# Qwiic_Quad_Relay.net
KiCad netlist of a schematic drawn in EAGLE
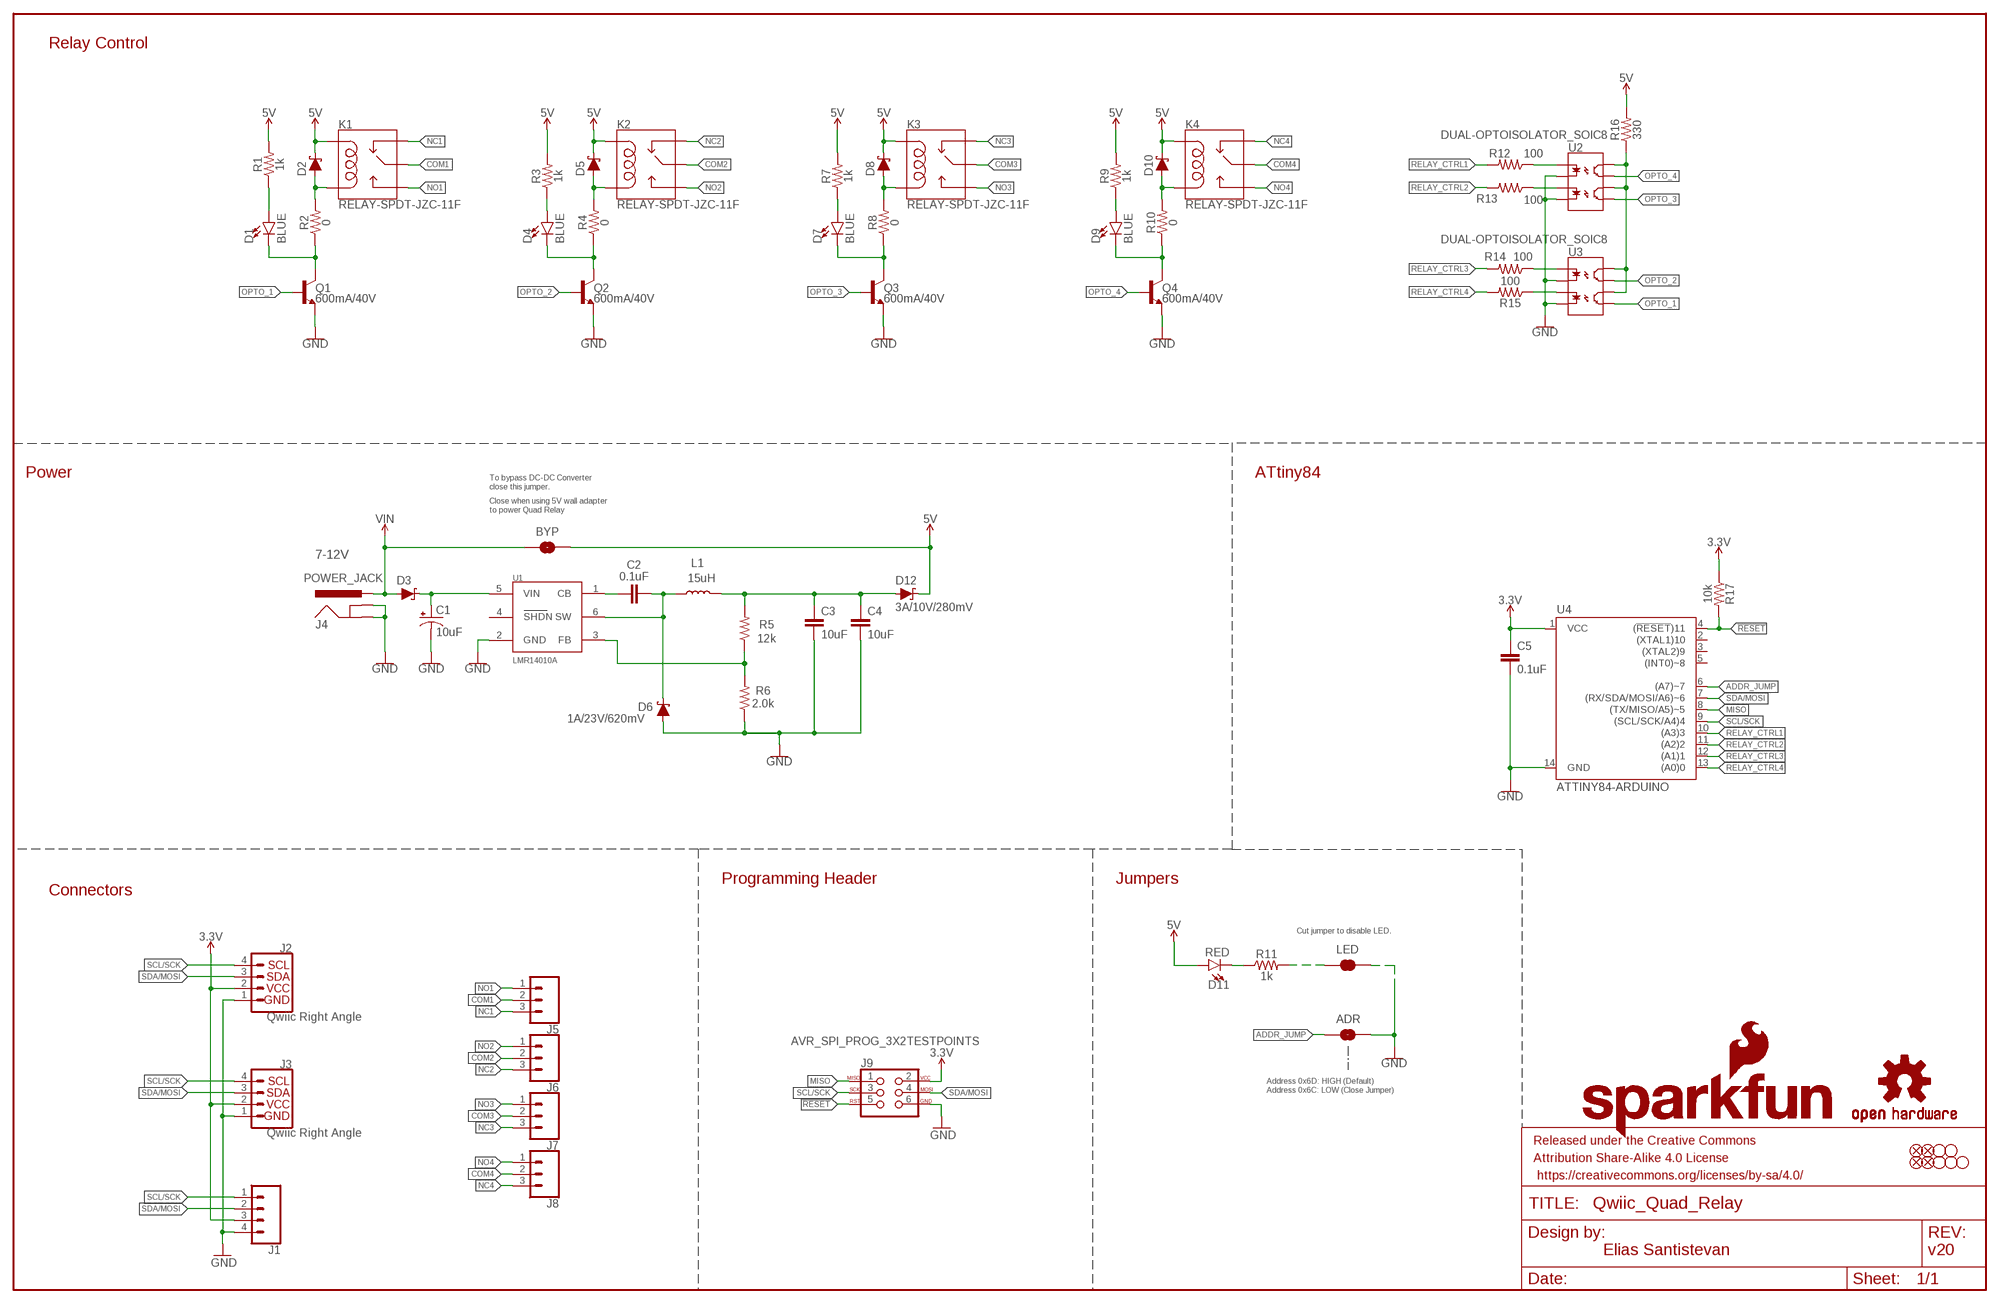
[diagram p0: schematic, sheet 1]

(export (version "E")
  (design (tool "Eeschema 10.0.6"))
  (components
    (comp (ref "ADR")
      (value "JUMPER-SMT_2_NO_SILK")
      (footprint "eagle-import:SMT-JUMPER_2_NO_SILK")
      (libsource (lib "eagle-import") (part "JUMPER-SMT_2_NO_SILK"))
    )
    (comp (ref "BYP")
      (value "JUMPER-SMT_2_NO_SILK")
      (footprint "eagle-import:SMT-JUMPER_2_NO_SILK")
      (libsource (lib "eagle-import") (part "JUMPER-SMT_2_NO_SILK"))
    )
    (comp (ref "C1")
      (value "10uF")
      (footprint "eagle-import:EIA3528")
      (libsource (lib "eagle-import") (part "10UF-POLAR-EIA3528-20V-10%(TANT)"))
    )
    (comp (ref "C2")
      (value "0.1uF")
      (footprint "eagle-import:0402")
      (libsource (lib "eagle-import") (part "0.1UF-0402-10V-10%-X7R"))
    )
    (comp (ref "C3")
      (value "10uF")
      (footprint "eagle-import:0603")
      (libsource (lib "eagle-import") (part "10UF-0603-6.3V-20%"))
    )
    (comp (ref "C4")
      (value "10uF")
      (footprint "eagle-import:0603")
      (libsource (lib "eagle-import") (part "10UF-0603-6.3V-20%"))
    )
    (comp (ref "C5")
      (value "0.1uF")
      (footprint "eagle-import:0603")
      (libsource (lib "eagle-import") (part "0.1UF-0603-25V-(+80/-20%)"))
    )
    (comp (ref "D1")
      (value "BLUE")
      (footprint "eagle-import:LED-0603")
      (libsource (lib "eagle-import") (part "LED-BLUE0603"))
    )
    (comp (ref "D2")
      (value "1A/23V/620mV")
      (footprint "eagle-import:SOD-323")
      (libsource (lib "eagle-import") (part "DIODE-SCHOTTKY-BAT20J"))
    )
    (comp (ref "D3")
      (value "1A/40V/500mV")
      (footprint "eagle-import:SMA-DIODE")
      (libsource (lib "eagle-import") (part "DIODE-SCHOTTKY-SS14"))
    )
    (comp (ref "D4")
      (value "BLUE")
      (footprint "eagle-import:LED-0603")
      (libsource (lib "eagle-import") (part "LED-BLUE0603"))
    )
    (comp (ref "D5")
      (value "1A/23V/620mV")
      (footprint "eagle-import:SOD-323")
      (libsource (lib "eagle-import") (part "DIODE-SCHOTTKY-BAT20J"))
    )
    (comp (ref "D6")
      (value "1A/23V/620mV")
      (footprint "eagle-import:SOD-323")
      (libsource (lib "eagle-import") (part "DIODE-SCHOTTKY-BAT20J"))
    )
    (comp (ref "D7")
      (value "BLUE")
      (footprint "eagle-import:LED-0603")
      (libsource (lib "eagle-import") (part "LED-BLUE0603"))
    )
    (comp (ref "D8")
      (value "1A/23V/620mV")
      (footprint "eagle-import:SOD-323")
      (libsource (lib "eagle-import") (part "DIODE-SCHOTTKY-BAT20J"))
    )
    (comp (ref "D9")
      (value "BLUE")
      (footprint "eagle-import:LED-0603")
      (libsource (lib "eagle-import") (part "LED-BLUE0603"))
    )
    (comp (ref "D10")
      (value "1A/23V/620mV")
      (footprint "eagle-import:SOD-323")
      (libsource (lib "eagle-import") (part "DIODE-SCHOTTKY-BAT20J"))
    )
    (comp (ref "D11")
      (value "RED")
      (footprint "eagle-import:LED-0603")
      (libsource (lib "eagle-import") (part "LED-RED0603"))
    )
    (comp (ref "D12")
      (value "3A/10V/280mV")
      (footprint "eagle-import:SOD-323")
      (libsource (lib "eagle-import") (part "DIODE-SCHOTTKY-BAT60A"))
    )
    (comp (ref "FD1")
      (value "FIDUCIAL1X2")
      (footprint "eagle-import:FIDUCIAL-1X2")
      (libsource (lib "eagle-import") (part "FIDUCIAL1X2"))
    )
    (comp (ref "FD2")
      (value "FIDUCIAL1X2")
      (footprint "eagle-import:FIDUCIAL-1X2")
      (libsource (lib "eagle-import") (part "FIDUCIAL1X2"))
    )
    (comp (ref "FD3")
      (value "FIDUCIAL1X2")
      (footprint "eagle-import:FIDUCIAL-1X2")
      (libsource (lib "eagle-import") (part "FIDUCIAL1X2"))
    )
    (comp (ref "FD4")
      (value "FIDUCIAL1X2")
      (footprint "eagle-import:FIDUCIAL-1X2")
      (libsource (lib "eagle-import") (part "FIDUCIAL1X2"))
    )
    (comp (ref "FRAME1")
      (value "FRAME-LEDGER")
      (footprint "eagle-import:CREATIVE_COMMONS")
      (libsource (lib "eagle-import") (part "FRAME-LEDGER"))
    )
    (comp (ref "J1")
      (value "CONN_041X04_NO_SILK_NO_POP")
      (footprint "eagle-import:1X04_NO_SILK")
      (libsource (lib "eagle-import") (part "CONN_041X04_NO_SILK_NO_POP"))
    )
    (comp (ref "J2")
      (value "Qwiic Right Angle")
      (footprint "eagle-import:JST04_1MM_RA")
      (libsource (lib "eagle-import") (part "I2C_STANDARDQWIIC"))
    )
    (comp (ref "J3")
      (value "Qwiic Right Angle")
      (footprint "eagle-import:JST04_1MM_RA")
      (libsource (lib "eagle-import") (part "I2C_STANDARDQWIIC"))
    )
    (comp (ref "J4")
      (value "POWER_JACK")
      (footprint "eagle-import:POWER_JACK_PTH")
      (libsource (lib "eagle-import") (part "POWER_JACK"))
    )
    (comp (ref "J5")
      (value "CONN_03-SCREW-5MM")
      (footprint "eagle-import:SCREWTERMINAL-5MM-3")
      (libsource (lib "eagle-import") (part "CONN_03-SCREW-5MM"))
    )
    (comp (ref "J6")
      (value "CONN_03-SCREW-5MM")
      (footprint "eagle-import:SCREWTERMINAL-5MM-3")
      (libsource (lib "eagle-import") (part "CONN_03-SCREW-5MM"))
    )
    (comp (ref "J7")
      (value "CONN_03-SCREW-5MM")
      (footprint "eagle-import:SCREWTERMINAL-5MM-3")
      (libsource (lib "eagle-import") (part "CONN_03-SCREW-5MM"))
    )
    (comp (ref "J8")
      (value "CONN_03-SCREW-5MM")
      (footprint "eagle-import:SCREWTERMINAL-5MM-3")
      (libsource (lib "eagle-import") (part "CONN_03-SCREW-5MM"))
    )
    (comp (ref "J9")
      (value "AVR_SPI_PROG_3X2TESTPOINTS")
      (footprint "eagle-import:2X3_TEST_POINTS")
      (libsource (lib "eagle-import") (part "AVR_SPI_PROG_3X2TESTPOINTS"))
    )
    (comp (ref "JP1")
      (value "STAND-OFF")
      (footprint "eagle-import:STAND-OFF")
      (libsource (lib "eagle-import") (part "STAND-OFF"))
    )
    (comp (ref "JP4")
      (value "STAND-OFF")
      (footprint "eagle-import:STAND-OFF")
      (libsource (lib "eagle-import") (part "STAND-OFF"))
    )
    (comp (ref "JP5")
      (value "STAND-OFF")
      (footprint "eagle-import:STAND-OFF")
      (libsource (lib "eagle-import") (part "STAND-OFF"))
    )
    (comp (ref "JP6")
      (value "STAND-OFF")
      (footprint "eagle-import:STAND-OFF")
      (libsource (lib "eagle-import") (part "STAND-OFF"))
    )
    (comp (ref "JP7")
      (value "STAND-OFF")
      (footprint "eagle-import:STAND-OFF")
      (libsource (lib "eagle-import") (part "STAND-OFF"))
    )
    (comp (ref "K1")
      (value "RELAY-SPDT-JZC-11F")
      (footprint "eagle-import:RELAY-JZC")
      (libsource (lib "eagle-import") (part "RELAY-SPDT-JZC-11F"))
    )
    (comp (ref "K2")
      (value "RELAY-SPDT-JZC-11F")
      (footprint "eagle-import:RELAY-JZC")
      (libsource (lib "eagle-import") (part "RELAY-SPDT-JZC-11F"))
    )
    (comp (ref "K3")
      (value "RELAY-SPDT-JZC-11F")
      (footprint "eagle-import:RELAY-JZC")
      (libsource (lib "eagle-import") (part "RELAY-SPDT-JZC-11F"))
    )
    (comp (ref "K4")
      (value "RELAY-SPDT-JZC-11F")
      (footprint "eagle-import:RELAY-JZC")
      (libsource (lib "eagle-import") (part "RELAY-SPDT-JZC-11F"))
    )
    (comp (ref "L1")
      (value "15uH")
      (footprint "eagle-import:INDUCTOR_15UH")
      (libsource (lib "eagle-import") (part "INDUCTOR-LQH5B-15UH"))
    )
    (comp (ref "LED")
      (value "JUMPER-SMT_2_NC_TRACE_SILK")
      (footprint "eagle-import:SMT-JUMPER_2_NC_TRACE_SILK")
      (libsource (lib "eagle-import") (part "JUMPER-SMT_2_NC_TRACE_SILK"))
    )
    (comp (ref "LOGO1")
      (value "SFE_LOGO_NAME_FLAME.1_INCH")
      (footprint "eagle-import:SFE_LOGO_NAME_FLAME_.1")
      (libsource (lib "eagle-import") (part "SFE_LOGO_NAME_FLAME.1_INCH"))
    )
    (comp (ref "LOGO2")
      (value "OSHW-LOGOS")
      (footprint "eagle-import:OSHW-LOGO-S")
      (libsource (lib "eagle-import") (part "OSHW-LOGOS"))
    )
    (comp (ref "Q1")
      (value "600mA/40V")
      (footprint "eagle-import:SOT23-3")
      (libsource (lib "eagle-import") (part "TRANS_NPN-MMBT2222AL"))
    )
    (comp (ref "Q2")
      (value "600mA/40V")
      (footprint "eagle-import:SOT23-3")
      (libsource (lib "eagle-import") (part "TRANS_NPN-MMBT2222AL"))
    )
    (comp (ref "Q3")
      (value "600mA/40V")
      (footprint "eagle-import:SOT23-3")
      (libsource (lib "eagle-import") (part "TRANS_NPN-MMBT2222AL"))
    )
    (comp (ref "Q4")
      (value "600mA/40V")
      (footprint "eagle-import:SOT23-3")
      (libsource (lib "eagle-import") (part "TRANS_NPN-MMBT2222AL"))
    )
    (comp (ref "R1")
      (value "1k")
      (footprint "eagle-import:0603")
      (libsource (lib "eagle-import") (part "1KOHM-0603-1/10W-1%"))
    )
    (comp (ref "R2")
      (value "0")
      (footprint "eagle-import:0603")
      (libsource (lib "eagle-import") (part "0OHM-0603-1/10W"))
    )
    (comp (ref "R3")
      (value "1k")
      (footprint "eagle-import:0603")
      (libsource (lib "eagle-import") (part "1KOHM-0603-1/10W-1%"))
    )
    (comp (ref "R4")
      (value "0")
      (footprint "eagle-import:0603")
      (libsource (lib "eagle-import") (part "0OHM-0603-1/10W"))
    )
    (comp (ref "R5")
      (value "12k")
      (footprint "eagle-import:0603")
      (libsource (lib "eagle-import") (part "12KOHM-0603-1/10W-1%"))
    )
    (comp (ref "R6")
      (value "2.0k")
      (footprint "eagle-import:0603")
      (libsource (lib "eagle-import") (part "2.0KOHM-0603-1/10W-5%"))
    )
    (comp (ref "R7")
      (value "1k")
      (footprint "eagle-import:0603")
      (libsource (lib "eagle-import") (part "1KOHM-0603-1/10W-1%"))
    )
    (comp (ref "R8")
      (value "0")
      (footprint "eagle-import:0603")
      (libsource (lib "eagle-import") (part "0OHM-0603-1/10W"))
    )
    (comp (ref "R9")
      (value "1k")
      (footprint "eagle-import:0603")
      (libsource (lib "eagle-import") (part "1KOHM-0603-1/10W-1%"))
    )
    (comp (ref "R10")
      (value "0")
      (footprint "eagle-import:0603")
      (libsource (lib "eagle-import") (part "0OHM-0603-1/10W"))
    )
    (comp (ref "R11")
      (value "1k")
      (footprint "eagle-import:0603")
      (libsource (lib "eagle-import") (part "1KOHM-0603-1/10W-1%"))
    )
    (comp (ref "R12")
      (value "100")
      (footprint "eagle-import:0603")
      (libsource (lib "eagle-import") (part "100OHM-0603-1/10W-1%"))
    )
    (comp (ref "R13")
      (value "100")
      (footprint "eagle-import:0603")
      (libsource (lib "eagle-import") (part "100OHM-0603-1/10W-1%"))
    )
    (comp (ref "R14")
      (value "100")
      (footprint "eagle-import:0603")
      (libsource (lib "eagle-import") (part "100OHM-0603-1/10W-1%"))
    )
    (comp (ref "R15")
      (value "100")
      (footprint "eagle-import:0603")
      (libsource (lib "eagle-import") (part "100OHM-0603-1/10W-1%"))
    )
    (comp (ref "R16")
      (value "330")
      (footprint "eagle-import:0603")
      (libsource (lib "eagle-import") (part "330OHM-0603-1/10W-1%"))
    )
    (comp (ref "R17")
      (value "10k")
      (footprint "eagle-import:0603")
      (libsource (lib "eagle-import") (part "10KOHM-0603-1/10W-1%"))
    )
    (comp (ref "U1")
      (value "LMR14010A")
      (footprint "eagle-import:SOT23-6")
      (libsource (lib "eagle-import") (part "LMR14010A"))
    )
    (comp (ref "U2")
      (value "DUAL-OPTOISOLATOR_SOIC8")
      (footprint "eagle-import:SO08")
      (libsource (lib "eagle-import") (part "DUAL-OPTOISOLATOR_SOIC8"))
    )
    (comp (ref "U3")
      (value "DUAL-OPTOISOLATOR_SOIC8")
      (footprint "eagle-import:SO08")
      (libsource (lib "eagle-import") (part "DUAL-OPTOISOLATOR_SOIC8"))
    )
    (comp (ref "U4")
      (value "ATTINY84-ARDUINO")
      (footprint "eagle-import:SO14")
      (libsource (lib "eagle-import") (part "ATTINY84-ARDUINO"))
    )
  )
  (nets
    (net (code "1") (name "/~{RESET}") (class "Default")
      (node (ref "J9") (pin "5") (pinfunction "5_5") (pintype "passive"))
      (node (ref "R17") (pin "2") (pinfunction "2_2") (pintype "passive"))
      (node (ref "U4") (pin "4") (pinfunction "(~{RESET})11_4") (pintype "bidirectional"))
    )
    (net (code "2") (name "3.3V") (class "Default")
      (node (ref "C5") (pin "1") (pinfunction "1_1") (pintype "passive"))
      (node (ref "J1") (pin "3") (pinfunction "3_3") (pintype "passive"))
      (node (ref "J2") (pin "2") (pinfunction "2_2") (pintype "power_in"))
      (node (ref "J3") (pin "2") (pinfunction "2_2") (pintype "power_in"))
      (node (ref "J9") (pin "2") (pinfunction "2_2") (pintype "passive"))
      (node (ref "R17") (pin "1") (pinfunction "1_1") (pintype "passive"))
      (node (ref "U4") (pin "1") (pinfunction "VCC_1") (pintype "bidirectional"))
    )
    (net (code "3") (name "5V") (class "Default")
      (node (ref "BYP") (pin "2") (pinfunction "2_2") (pintype "passive"))
      (node (ref "D10") (pin "C") (pinfunction "C_C") (pintype "passive"))
      (node (ref "D11") (pin "A") (pinfunction "A_A") (pintype "passive"))
      (node (ref "D12") (pin "C") (pinfunction "C_C") (pintype "passive"))
      (node (ref "D2") (pin "C") (pinfunction "C_C") (pintype "passive"))
      (node (ref "D5") (pin "C") (pinfunction "C_C") (pintype "passive"))
      (node (ref "D8") (pin "C") (pinfunction "C_C") (pintype "passive"))
      (node (ref "K1") (pin "5") (pinfunction "COIL1_5") (pintype "bidirectional"))
      (node (ref "K2") (pin "5") (pinfunction "COIL1_5") (pintype "bidirectional"))
      (node (ref "K3") (pin "5") (pinfunction "COIL1_5") (pintype "bidirectional"))
      (node (ref "K4") (pin "5") (pinfunction "COIL1_5") (pintype "bidirectional"))
      (node (ref "R1") (pin "2") (pinfunction "2_2") (pintype "passive"))
      (node (ref "R16") (pin "2") (pinfunction "2_2") (pintype "passive"))
      (node (ref "R3") (pin "2") (pinfunction "2_2") (pintype "passive"))
      (node (ref "R7") (pin "2") (pinfunction "2_2") (pintype "passive"))
      (node (ref "R9") (pin "2") (pinfunction "2_2") (pintype "passive"))
    )
    (net (code "4") (name "ADDR_JUMP") (class "Default")
      (node (ref "ADR") (pin "1") (pinfunction "1_1") (pintype "passive"))
      (node (ref "U4") (pin "6") (pinfunction "(A7)~{7}_6") (pintype "bidirectional"))
    )
    (net (code "5") (name "COM1") (class "Default")
      (node (ref "J5") (pin "2") (pinfunction "2_2") (pintype "passive"))
      (node (ref "K1") (pin "4") (pinfunction "MAIN_4") (pintype "bidirectional"))
    )
    (net (code "6") (name "COM2") (class "Default")
      (node (ref "J6") (pin "2") (pinfunction "2_2") (pintype "passive"))
      (node (ref "K2") (pin "4") (pinfunction "MAIN_4") (pintype "bidirectional"))
    )
    (net (code "7") (name "COM3") (class "Default")
      (node (ref "J7") (pin "2") (pinfunction "2_2") (pintype "passive"))
      (node (ref "K3") (pin "4") (pinfunction "MAIN_4") (pintype "bidirectional"))
    )
    (net (code "8") (name "COM4") (class "Default")
      (node (ref "J8") (pin "2") (pinfunction "2_2") (pintype "passive"))
      (node (ref "K4") (pin "4") (pinfunction "MAIN_4") (pintype "bidirectional"))
    )
    (net (code "9") (name "GND") (class "Default")
      (node (ref "ADR") (pin "2") (pinfunction "2_2") (pintype "passive"))
      (node (ref "C1") (pin "C") (pinfunction "-_C") (pintype "passive"))
      (node (ref "C3") (pin "2") (pinfunction "2_2") (pintype "passive"))
      (node (ref "C4") (pin "2") (pinfunction "2_2") (pintype "passive"))
      (node (ref "C5") (pin "2") (pinfunction "2_2") (pintype "passive"))
      (node (ref "D6") (pin "A") (pinfunction "A_A") (pintype "passive"))
      (node (ref "J1") (pin "4") (pinfunction "4_4") (pintype "passive"))
      (node (ref "J2") (pin "1") (pinfunction "1_1") (pintype "power_in"))
      (node (ref "J3") (pin "1") (pinfunction "1_1") (pintype "power_in"))
      (node (ref "J4") (pin "GND") (pinfunction "GND_GND") (pintype "bidirectional"))
      (node (ref "J4") (pin "GNDBREAK") (pinfunction "GNDBREAK_GNDBREAK") (pintype "bidirectional"))
      (node (ref "J9") (pin "6") (pinfunction "6_6") (pintype "passive"))
      (node (ref "LED") (pin "1") (pinfunction "1_1") (pintype "passive"))
      (node (ref "Q1") (pin "2") (pinfunction "E_2") (pintype "passive"))
      (node (ref "Q2") (pin "2") (pinfunction "E_2") (pintype "passive"))
      (node (ref "Q3") (pin "2") (pinfunction "E_2") (pintype "passive"))
      (node (ref "Q4") (pin "2") (pinfunction "E_2") (pintype "passive"))
      (node (ref "R6") (pin "1") (pinfunction "1_1") (pintype "passive"))
      (node (ref "U1") (pin "2") (pinfunction "GND_2") (pintype "power_in"))
      (node (ref "U2") (pin "2") (pinfunction "C1_2") (pintype "bidirectional"))
      (node (ref "U2") (pin "4") (pinfunction "C2_4") (pintype "bidirectional"))
      (node (ref "U3") (pin "2") (pinfunction "C1_2") (pintype "bidirectional"))
      (node (ref "U3") (pin "4") (pinfunction "C2_4") (pintype "bidirectional"))
      (node (ref "U4") (pin "14") (pinfunction "GND_14") (pintype "bidirectional"))
    )
    (net (code "10") (name "MISO") (class "Default")
      (node (ref "J9") (pin "1") (pinfunction "1_1") (pintype "passive"))
      (node (ref "U4") (pin "8") (pinfunction "(TX/MISO/A5)~{5}_8") (pintype "bidirectional"))
    )
    (net (code "11") (name "NC1") (class "Default")
      (node (ref "J5") (pin "3") (pinfunction "3_3") (pintype "passive"))
      (node (ref "K1") (pin "2") (pinfunction "NC_2") (pintype "bidirectional"))
    )
    (net (code "12") (name "NC2") (class "Default")
      (node (ref "J6") (pin "3") (pinfunction "3_3") (pintype "passive"))
      (node (ref "K2") (pin "2") (pinfunction "NC_2") (pintype "bidirectional"))
    )
    (net (code "13") (name "NC3") (class "Default")
      (node (ref "J7") (pin "3") (pinfunction "3_3") (pintype "passive"))
      (node (ref "K3") (pin "2") (pinfunction "NC_2") (pintype "bidirectional"))
    )
    (net (code "14") (name "NC4") (class "Default")
      (node (ref "J8") (pin "3") (pinfunction "3_3") (pintype "passive"))
      (node (ref "K4") (pin "2") (pinfunction "NC_2") (pintype "bidirectional"))
    )
    (net (code "15") (name "NO1") (class "Default")
      (node (ref "J5") (pin "1") (pinfunction "1_1") (pintype "passive"))
      (node (ref "K1") (pin "3") (pinfunction "NO_3") (pintype "bidirectional"))
    )
    (net (code "16") (name "NO2") (class "Default")
      (node (ref "J6") (pin "1") (pinfunction "1_1") (pintype "passive"))
      (node (ref "K2") (pin "3") (pinfunction "NO_3") (pintype "bidirectional"))
    )
    (net (code "17") (name "NO3") (class "Default")
      (node (ref "J7") (pin "1") (pinfunction "1_1") (pintype "passive"))
      (node (ref "K3") (pin "3") (pinfunction "NO_3") (pintype "bidirectional"))
    )
    (net (code "18") (name "NO4") (class "Default")
      (node (ref "J8") (pin "1") (pinfunction "1_1") (pintype "passive"))
      (node (ref "K4") (pin "3") (pinfunction "NO_3") (pintype "bidirectional"))
    )
    (net (code "19") (name "Net-(C1-+)") (class "Default")
      (node (ref "C1") (pin "A") (pinfunction "+_A") (pintype "passive"))
      (node (ref "D3") (pin "C") (pinfunction "C_C") (pintype "passive"))
      (node (ref "U1") (pin "5") (pinfunction "VIN_5") (pintype "power_in"))
    )
    (net (code "20") (name "Net-(D1-PadA)") (class "Default")
      (node (ref "D1") (pin "A") (pinfunction "A_A") (pintype "passive"))
      (node (ref "R1") (pin "1") (pinfunction "1_1") (pintype "passive"))
    )
    (net (code "21") (name "Net-(D4-PadA)") (class "Default")
      (node (ref "D4") (pin "A") (pinfunction "A_A") (pintype "passive"))
      (node (ref "R3") (pin "1") (pinfunction "1_1") (pintype "passive"))
    )
    (net (code "22") (name "Net-(D7-PadA)") (class "Default")
      (node (ref "D7") (pin "A") (pinfunction "A_A") (pintype "passive"))
      (node (ref "R7") (pin "1") (pinfunction "1_1") (pintype "passive"))
    )
    (net (code "23") (name "Net-(D9-PadA)") (class "Default")
      (node (ref "D9") (pin "A") (pinfunction "A_A") (pintype "passive"))
      (node (ref "R9") (pin "1") (pinfunction "1_1") (pintype "passive"))
    )
    (net (code "24") (name "Net-(D11-PadC)") (class "Default")
      (node (ref "D11") (pin "C") (pinfunction "C_C") (pintype "passive"))
      (node (ref "R11") (pin "1") (pinfunction "1_1") (pintype "passive"))
    )
    (net (code "25") (name "Net-(K1-COIL2)") (class "Default")
      (node (ref "D2") (pin "A") (pinfunction "A_A") (pintype "passive"))
      (node (ref "K1") (pin "1") (pinfunction "COIL2_1") (pintype "bidirectional"))
      (node (ref "R2") (pin "2") (pinfunction "2_2") (pintype "passive"))
    )
    (net (code "26") (name "Net-(K2-COIL2)") (class "Default")
      (node (ref "D5") (pin "A") (pinfunction "A_A") (pintype "passive"))
      (node (ref "K2") (pin "1") (pinfunction "COIL2_1") (pintype "bidirectional"))
      (node (ref "R4") (pin "2") (pinfunction "2_2") (pintype "passive"))
    )
    (net (code "27") (name "Net-(K3-COIL2)") (class "Default")
      (node (ref "D8") (pin "A") (pinfunction "A_A") (pintype "passive"))
      (node (ref "K3") (pin "1") (pinfunction "COIL2_1") (pintype "bidirectional"))
      (node (ref "R8") (pin "2") (pinfunction "2_2") (pintype "passive"))
    )
    (net (code "28") (name "Net-(K4-COIL2)") (class "Default")
      (node (ref "D10") (pin "A") (pinfunction "A_A") (pintype "passive"))
      (node (ref "K4") (pin "1") (pinfunction "COIL2_1") (pintype "bidirectional"))
      (node (ref "R10") (pin "2") (pinfunction "2_2") (pintype "passive"))
    )
    (net (code "29") (name "Net-(L1-1)") (class "Default")
      (node (ref "C2") (pin "2") (pinfunction "2_2") (pintype "passive"))
      (node (ref "D6") (pin "C") (pinfunction "C_C") (pintype "passive"))
      (node (ref "L1") (pin "P1") (pinfunction "1_P1") (pintype "passive"))
      (node (ref "U1") (pin "6") (pinfunction "SW_6") (pintype "power_in"))
    )
    (net (code "30") (name "Net-(L1-2)") (class "Default")
      (node (ref "C3") (pin "1") (pinfunction "1_1") (pintype "passive"))
      (node (ref "C4") (pin "1") (pinfunction "1_1") (pintype "passive"))
      (node (ref "D12") (pin "A") (pinfunction "A_A") (pintype "passive"))
      (node (ref "L1") (pin "P2") (pinfunction "2_P2") (pintype "passive"))
      (node (ref "R5") (pin "2") (pinfunction "2_2") (pintype "passive"))
    )
    (net (code "31") (name "Net-(LED-Pad2)") (class "Default")
      (node (ref "LED") (pin "2") (pinfunction "2_2") (pintype "passive"))
      (node (ref "R11") (pin "2") (pinfunction "2_2") (pintype "passive"))
    )
    (net (code "32") (name "Net-(Q1-C)") (class "Default")
      (node (ref "D1") (pin "C") (pinfunction "C_C") (pintype "passive"))
      (node (ref "Q1") (pin "3") (pinfunction "C_3") (pintype "passive"))
      (node (ref "R2") (pin "1") (pinfunction "1_1") (pintype "passive"))
    )
    (net (code "33") (name "Net-(Q2-C)") (class "Default")
      (node (ref "D4") (pin "C") (pinfunction "C_C") (pintype "passive"))
      (node (ref "Q2") (pin "3") (pinfunction "C_3") (pintype "passive"))
      (node (ref "R4") (pin "1") (pinfunction "1_1") (pintype "passive"))
    )
    (net (code "34") (name "Net-(Q3-C)") (class "Default")
      (node (ref "D7") (pin "C") (pinfunction "C_C") (pintype "passive"))
      (node (ref "Q3") (pin "3") (pinfunction "C_3") (pintype "passive"))
      (node (ref "R8") (pin "1") (pinfunction "1_1") (pintype "passive"))
    )
    (net (code "35") (name "Net-(Q4-C)") (class "Default")
      (node (ref "D9") (pin "C") (pinfunction "C_C") (pintype "passive"))
      (node (ref "Q4") (pin "3") (pinfunction "C_3") (pintype "passive"))
      (node (ref "R10") (pin "1") (pinfunction "1_1") (pintype "passive"))
    )
    (net (code "36") (name "Net-(U1-CB)") (class "Default")
      (node (ref "C2") (pin "1") (pinfunction "1_1") (pintype "passive"))
      (node (ref "U1") (pin "1") (pinfunction "CB_1") (pintype "input"))
    )
    (net (code "37") (name "Net-(U1-FB)") (class "Default")
      (node (ref "R5") (pin "1") (pinfunction "1_1") (pintype "passive"))
      (node (ref "R6") (pin "2") (pinfunction "2_2") (pintype "passive"))
      (node (ref "U1") (pin "3") (pinfunction "FB_3") (pintype "input"))
    )
    (net (code "38") (name "Net-(U2-A1)") (class "Default")
      (node (ref "R12") (pin "1") (pinfunction "1_1") (pintype "passive"))
      (node (ref "U2") (pin "1") (pinfunction "A1_1") (pintype "bidirectional"))
    )
    (net (code "39") (name "Net-(U2-A2)") (class "Default")
      (node (ref "R13") (pin "1") (pinfunction "1_1") (pintype "passive"))
      (node (ref "U2") (pin "3") (pinfunction "A2_3") (pintype "bidirectional"))
    )
    (net (code "40") (name "Net-(U2-CL1)") (class "Default")
      (node (ref "R16") (pin "1") (pinfunction "1_1") (pintype "passive"))
      (node (ref "U2") (pin "6") (pinfunction "CL2_6") (pintype "bidirectional"))
      (node (ref "U2") (pin "8") (pinfunction "CL1_8") (pintype "bidirectional"))
      (node (ref "U3") (pin "6") (pinfunction "CL2_6") (pintype "bidirectional"))
      (node (ref "U3") (pin "8") (pinfunction "CL1_8") (pintype "bidirectional"))
    )
    (net (code "41") (name "Net-(U3-A1)") (class "Default")
      (node (ref "R14") (pin "1") (pinfunction "1_1") (pintype "passive"))
      (node (ref "U3") (pin "1") (pinfunction "A1_1") (pintype "bidirectional"))
    )
    (net (code "42") (name "Net-(U3-A2)") (class "Default")
      (node (ref "R15") (pin "1") (pinfunction "1_1") (pintype "passive"))
      (node (ref "U3") (pin "3") (pinfunction "A2_3") (pintype "bidirectional"))
    )
    (net (code "43") (name "OPTO_1") (class "Default")
      (node (ref "Q1") (pin "1") (pinfunction "B_1") (pintype "passive"))
      (node (ref "U3") (pin "5") (pinfunction "EM2_5") (pintype "bidirectional"))
    )
    (net (code "44") (name "OPTO_2") (class "Default")
      (node (ref "Q2") (pin "1") (pinfunction "B_1") (pintype "passive"))
      (node (ref "U3") (pin "7") (pinfunction "EM1_7") (pintype "bidirectional"))
    )
    (net (code "45") (name "OPTO_3") (class "Default")
      (node (ref "Q3") (pin "1") (pinfunction "B_1") (pintype "passive"))
      (node (ref "U2") (pin "5") (pinfunction "EM2_5") (pintype "bidirectional"))
    )
    (net (code "46") (name "OPTO_4") (class "Default")
      (node (ref "Q4") (pin "1") (pinfunction "B_1") (pintype "passive"))
      (node (ref "U2") (pin "7") (pinfunction "EM1_7") (pintype "bidirectional"))
    )
    (net (code "47") (name "RELAY_CTRL1") (class "Default")
      (node (ref "R12") (pin "2") (pinfunction "2_2") (pintype "passive"))
      (node (ref "U4") (pin "10") (pinfunction "(A3)3_10") (pintype "bidirectional"))
    )
    (net (code "48") (name "RELAY_CTRL2") (class "Default")
      (node (ref "R13") (pin "2") (pinfunction "2_2") (pintype "passive"))
      (node (ref "U4") (pin "11") (pinfunction "(A2)2_11") (pintype "bidirectional"))
    )
    (net (code "49") (name "RELAY_CTRL3") (class "Default")
      (node (ref "R14") (pin "2") (pinfunction "2_2") (pintype "passive"))
      (node (ref "U4") (pin "12") (pinfunction "(A1)1_12") (pintype "bidirectional"))
    )
    (net (code "50") (name "RELAY_CTRL4") (class "Default")
      (node (ref "R15") (pin "2") (pinfunction "2_2") (pintype "passive"))
      (node (ref "U4") (pin "13") (pinfunction "(A0)0_13") (pintype "bidirectional"))
    )
    (net (code "51") (name "SCL{slash}SCK") (class "Default")
      (node (ref "J1") (pin "1") (pinfunction "1_1") (pintype "passive"))
      (node (ref "J2") (pin "4") (pinfunction "4_4") (pintype "passive"))
      (node (ref "J3") (pin "4") (pinfunction "4_4") (pintype "passive"))
      (node (ref "J9") (pin "3") (pinfunction "3_3") (pintype "passive"))
      (node (ref "U4") (pin "9") (pinfunction "(SCL/SCK/A4)4_9") (pintype "bidirectional"))
    )
    (net (code "52") (name "SDA{slash}MOSI") (class "Default")
      (node (ref "J1") (pin "2") (pinfunction "2_2") (pintype "passive"))
      (node (ref "J2") (pin "3") (pinfunction "3_3") (pintype "passive"))
      (node (ref "J3") (pin "3") (pinfunction "3_3") (pintype "passive"))
      (node (ref "J9") (pin "4") (pinfunction "4_4") (pintype "passive"))
      (node (ref "U4") (pin "7") (pinfunction "(RX/SDA/MOSI/A6)~{6}_7") (pintype "bidirectional"))
    )
    (net (code "53") (name "VIN") (class "Default")
      (node (ref "BYP") (pin "1") (pinfunction "1_1") (pintype "passive"))
      (node (ref "D3") (pin "A") (pinfunction "A_A") (pintype "passive"))
      (node (ref "J4") (pin "PWR") (pinfunction "PWR_PWR") (pintype "bidirectional"))
    )
    (net (code "54") (name "unconnected-(U1-SHDN-Pad4)") (class "Default")
      (node (ref "U1") (pin "4") (pinfunction "SHDN_4") (pintype "input"))
    )
    (net (code "55") (name "unconnected-(U4-(INT0)~{8}-Pad5)") (class "Default")
      (node (ref "U4") (pin "5") (pinfunction "(INT0)~{8}_5") (pintype "bidirectional"))
    )
    (net (code "56") (name "unconnected-(U4-(XTAL1)10-Pad2)") (class "Default")
      (node (ref "U4") (pin "2") (pinfunction "(XTAL1)10_2") (pintype "bidirectional"))
    )
    (net (code "57") (name "unconnected-(U4-(XTAL2)9-Pad3)") (class "Default")
      (node (ref "U4") (pin "3") (pinfunction "(XTAL2)9_3") (pintype "bidirectional"))
    )
  )
)
